# expansion.net
KiCad netlist of a schematic drawn in EAGLE
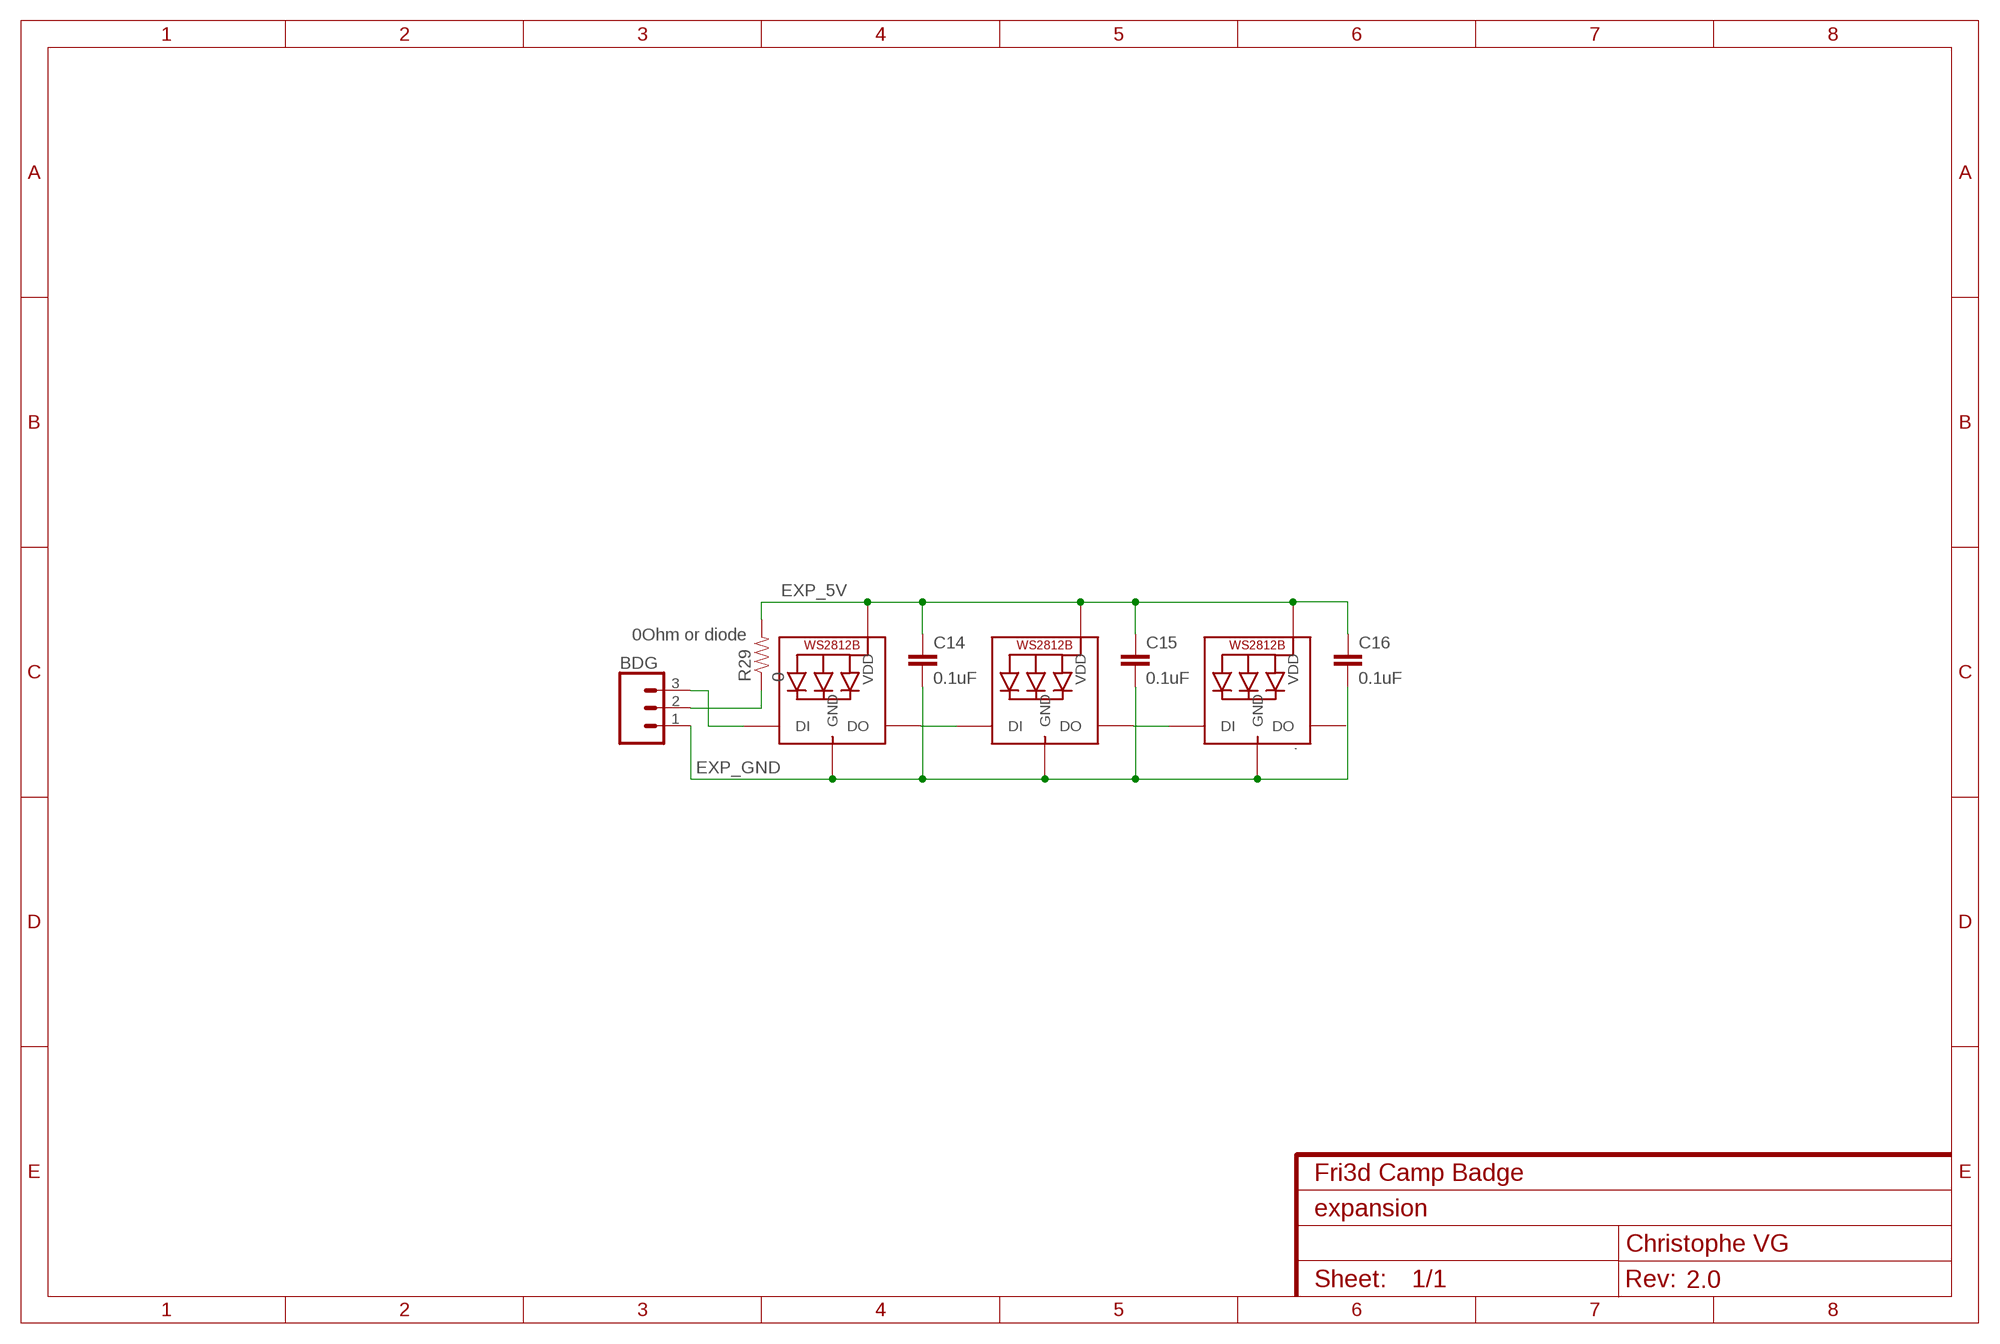
[diagram p0: schematic, sheet 1]

(export (version "E")
  (design (tool "Eeschema 10.0.6"))
  (components
    (comp (ref "BDG")
      (value "CONN_03")
      (footprint "eagle-import:1X03")
      (libsource (lib "eagle-import") (part "CONN_03"))
    )
    (comp (ref "C14")
      (value "0.1uF")
      (footprint "eagle-import:0805")
      (libsource (lib "eagle-import") (part "CAP0805"))
    )
    (comp (ref "C15")
      (value "0.1uF")
      (footprint "eagle-import:0805")
      (libsource (lib "eagle-import") (part "CAP0805"))
    )
    (comp (ref "C16")
      (value "0.1uF")
      (footprint "eagle-import:0805")
      (libsource (lib "eagle-import") (part "CAP0805"))
    )
    (comp (ref "R29")
      (value "0")
      (footprint "eagle-import:0805")
      (libsource (lib "eagle-import") (part "RESISTOR0805-RES"))
    )
    (comp (ref "WS1")
      (value "WS2812B5050")
      (footprint "eagle-import:WS2812B")
      (libsource (lib "eagle-import") (part "WS2812B5050"))
    )
    (comp (ref "WS2")
      (value "WS2812B5050")
      (footprint "eagle-import:WS2812B")
      (libsource (lib "eagle-import") (part "WS2812B5050"))
    )
    (comp (ref "WS3")
      (value "WS2812B5050")
      (footprint "eagle-import:WS2812B")
      (libsource (lib "eagle-import") (part "WS2812B5050"))
    )
  )
  (nets
    (net (code "1") (name "/EXP_5V") (class "Default")
      (node (ref "C14") (pin "1") (pinfunction "1_1") (pintype "passive"))
      (node (ref "C15") (pin "1") (pinfunction "1_1") (pintype "passive"))
      (node (ref "C16") (pin "1") (pinfunction "1_1") (pintype "passive"))
      (node (ref "R29") (pin "2") (pinfunction "2_2") (pintype "passive"))
      (node (ref "WS1") (pin "1-VDD") (pinfunction "VDD_1-VDD") (pintype "power_in"))
      (node (ref "WS2") (pin "1-VDD") (pinfunction "VDD_1-VDD") (pintype "power_in"))
      (node (ref "WS3") (pin "1-VDD") (pinfunction "VDD_1-VDD") (pintype "power_in"))
    )
    (net (code "2") (name "/EXP_GND") (class "Default")
      (node (ref "BDG") (pin "1") (pinfunction "1_1") (pintype "passive"))
      (node (ref "C14") (pin "2") (pinfunction "2_2") (pintype "passive"))
      (node (ref "C15") (pin "2") (pinfunction "2_2") (pintype "passive"))
      (node (ref "C16") (pin "2") (pinfunction "2_2") (pintype "passive"))
      (node (ref "WS1") (pin "3-GND") (pinfunction "GND_3-GND") (pintype "power_in"))
      (node (ref "WS2") (pin "3-GND") (pinfunction "GND_3-GND") (pintype "power_in"))
      (node (ref "WS3") (pin "3-GND") (pinfunction "GND_3-GND") (pintype "power_in"))
    )
    (net (code "3") (name "Net-(BDG-Pad2)") (class "Default")
      (node (ref "BDG") (pin "2") (pinfunction "2_2") (pintype "passive"))
      (node (ref "R29") (pin "1") (pinfunction "1_1") (pintype "passive"))
    )
    (net (code "4") (name "Net-(WS1-DI)") (class "Default")
      (node (ref "BDG") (pin "3") (pinfunction "3_3") (pintype "passive"))
      (node (ref "WS1") (pin "4-DIN") (pinfunction "DI_4-DIN") (pintype "input"))
    )
    (net (code "5") (name "Net-(WS1-DO)") (class "Default")
      (node (ref "WS1") (pin "2-DOUT") (pinfunction "DO_2-DOUT") (pintype "output"))
      (node (ref "WS2") (pin "4-DIN") (pinfunction "DI_4-DIN") (pintype "input"))
    )
    (net (code "6") (name "Net-(WS2-DO)") (class "Default")
      (node (ref "WS2") (pin "2-DOUT") (pinfunction "DO_2-DOUT") (pintype "output"))
      (node (ref "WS3") (pin "4-DIN") (pinfunction "DI_4-DIN") (pintype "input"))
    )
    (net (code "7") (name "unconnected-(WS3-DO-Pad2-DOUT)") (class "Default")
      (node (ref "WS3") (pin "2-DOUT") (pinfunction "DO_2-DOUT") (pintype "output"))
    )
  )
)
